# atx_distributor_v1_0.net
KiCad netlist of a schematic drawn in EAGLE
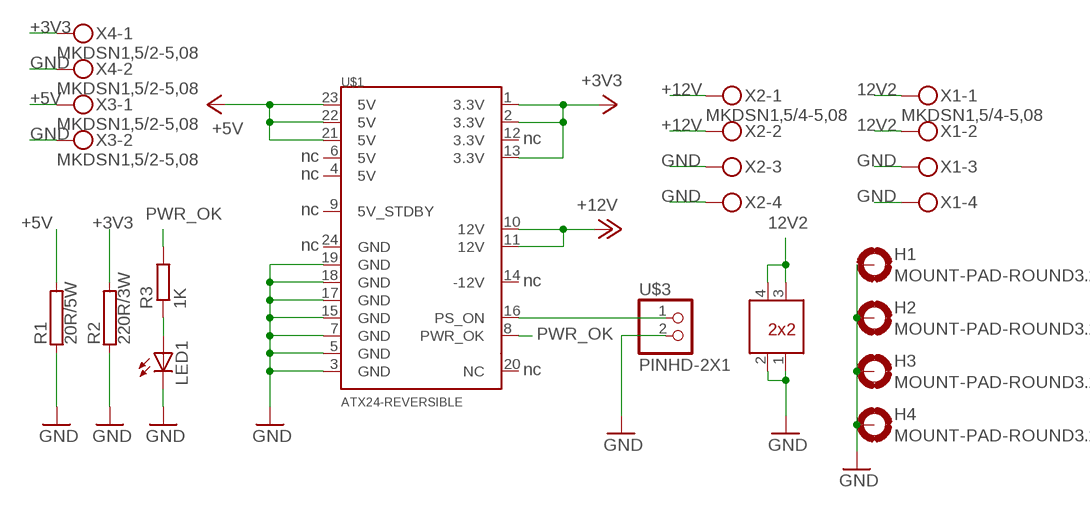
[diagram p0: schematic, sheet 1]

(export (version "E")
  (design (tool "Eeschema 10.0.6"))
  (components
    (comp (ref "H1")
      (value "MOUNT-PAD-ROUND3.2")
      (footprint "eagle-import:3,2-PAD")
      (libsource (lib "eagle-import") (part "MOUNT-PAD-ROUND3.2"))
    )
    (comp (ref "H2")
      (value "MOUNT-PAD-ROUND3.2")
      (footprint "eagle-import:3,2-PAD")
      (libsource (lib "eagle-import") (part "MOUNT-PAD-ROUND3.2"))
    )
    (comp (ref "H3")
      (value "MOUNT-PAD-ROUND3.2")
      (footprint "eagle-import:3,2-PAD")
      (libsource (lib "eagle-import") (part "MOUNT-PAD-ROUND3.2"))
    )
    (comp (ref "H4")
      (value "MOUNT-PAD-ROUND3.2")
      (footprint "eagle-import:3,2-PAD")
      (libsource (lib "eagle-import") (part "MOUNT-PAD-ROUND3.2"))
    )
    (comp (ref "LED1")
      (value "LED3MM")
      (footprint "eagle-import:LED3MM")
      (libsource (lib "eagle-import") (part "LED3MM"))
    )
    (comp (ref "R1")
      (value "20R/5W")
      (footprint "eagle-import:HPS923")
      (libsource (lib "eagle-import") (part "RHPS923"))
    )
    (comp (ref "R2")
      (value "220R/3W")
      (footprint "eagle-import:CA4050")
      (libsource (lib "eagle-import") (part "RCA4050"))
    )
    (comp (ref "R3")
      (value "1K")
      (footprint "eagle-import:0207_10")
      (libsource (lib "eagle-import") (part "R-EU_0207/10"))
    )
    (comp (ref "U$1")
      (value "ATX24-REVERSIBLE")
      (footprint "eagle-import:ATX24")
      (libsource (lib "eagle-import") (part "ATX24-REVERSIBLE"))
    )
    (comp (ref "U$2")
      (value "ATX2X2")
      (footprint "eagle-import:ATX2X2")
      (libsource (lib "eagle-import") (part "ATX2X2"))
    )
    (comp (ref "U$3")
      (value "PINHD-2X1")
      (footprint "eagle-import:PINHD-2X1")
      (libsource (lib "eagle-import") (part "PINHD-2X1"))
    )
    (comp (ref "X1")
      (value "MKDSN1,5/4-5,08")
      (footprint "eagle-import:MKDSN1,5_4-5,08")
      (fields (field (name "MPN") "SMKDSN1,5/4-5,08"))
      (libsource (lib "eagle-import") (part "MKDSN1,5/4-5,08"))
    )
    (comp (ref "X2")
      (value "MKDSN1,5/4-5,08")
      (footprint "eagle-import:MKDSN1,5_4-5,08")
      (fields (field (name "MPN") "SMKDSN1,5/4-5,08"))
      (libsource (lib "eagle-import") (part "MKDSN1,5/4-5,08"))
    )
    (comp (ref "X3")
      (value "MKDSN1,5/2-5,08")
      (footprint "eagle-import:MKDSN1,5_2-5,08")
      (fields (field (name "MPN") "MKDSN 1,5/2-5.08"))
      (libsource (lib "eagle-import") (part "MKDSN1,5/2-5,08"))
    )
    (comp (ref "X4")
      (value "MKDSN1,5/2-5,08")
      (footprint "eagle-import:MKDSN1,5_2-5,08")
      (fields (field (name "MPN") "MKDSN 1,5/2-5.08"))
      (libsource (lib "eagle-import") (part "MKDSN1,5/2-5,08"))
    )
  )
  (nets
    (net (code "1") (name "+3V3") (class "Default")
      (node (ref "R2") (pin "2") (pinfunction "2_2") (pintype "passive"))
      (node (ref "U$1") (pin "1") (pinfunction "3.3V_1") (pintype "bidirectional"))
      (node (ref "U$1") (pin "13") (pinfunction "3.3V_13") (pintype "bidirectional"))
      (node (ref "U$1") (pin "2") (pinfunction "3.3V_2") (pintype "bidirectional"))
      (node (ref "X4") (pin "1") (pinfunction "KL_1") (pintype "passive"))
    )
    (net (code "2") (name "+5V") (class "Default")
      (node (ref "R1") (pin "2") (pinfunction "2_2") (pintype "passive"))
      (node (ref "U$1") (pin "21") (pinfunction "5V_21") (pintype "bidirectional"))
      (node (ref "U$1") (pin "22") (pinfunction "5V_22") (pintype "bidirectional"))
      (node (ref "U$1") (pin "23") (pinfunction "5V_23") (pintype "bidirectional"))
      (node (ref "X3") (pin "1") (pinfunction "KL_1") (pintype "passive"))
    )
    (net (code "3") (name "+12V") (class "Default")
      (node (ref "U$1") (pin "10") (pinfunction "12V_10") (pintype "bidirectional"))
      (node (ref "U$1") (pin "11") (pinfunction "12V_11") (pintype "bidirectional"))
      (node (ref "X2") (pin "1") (pinfunction "KL_1") (pintype "passive"))
      (node (ref "X2") (pin "2") (pinfunction "KL_2") (pintype "passive"))
    )
    (net (code "4") (name "/12V2") (class "Default")
      (node (ref "U$2") (pin "3") (pinfunction "P$3_3") (pintype "bidirectional"))
      (node (ref "U$2") (pin "4") (pinfunction "P$4_4") (pintype "bidirectional"))
      (node (ref "X1") (pin "1") (pinfunction "KL_1") (pintype "passive"))
      (node (ref "X1") (pin "2") (pinfunction "KL_2") (pintype "passive"))
    )
    (net (code "5") (name "/PWR_OK") (class "Default")
      (node (ref "R3") (pin "2") (pinfunction "2_2") (pintype "passive"))
      (node (ref "U$1") (pin "8") (pinfunction "PWR_OK_8") (pintype "bidirectional"))
    )
    (net (code "6") (name "GND") (class "Default")
      (node (ref "H1") (pin "B3,2") (pinfunction "MOUNT_B3,2") (pintype "passive"))
      (node (ref "H2") (pin "B3,2") (pinfunction "MOUNT_B3,2") (pintype "passive"))
      (node (ref "H3") (pin "B3,2") (pinfunction "MOUNT_B3,2") (pintype "passive"))
      (node (ref "H4") (pin "B3,2") (pinfunction "MOUNT_B3,2") (pintype "passive"))
      (node (ref "LED1") (pin "K") (pinfunction "C_K") (pintype "passive"))
      (node (ref "R1") (pin "1") (pinfunction "1_1") (pintype "passive"))
      (node (ref "R2") (pin "1") (pinfunction "1_1") (pintype "passive"))
      (node (ref "U$1") (pin "15") (pinfunction "GND_15") (pintype "bidirectional"))
      (node (ref "U$1") (pin "17") (pinfunction "GND_17") (pintype "bidirectional"))
      (node (ref "U$1") (pin "18") (pinfunction "GND_18") (pintype "bidirectional"))
      (node (ref "U$1") (pin "19") (pinfunction "GND_19") (pintype "bidirectional"))
      (node (ref "U$1") (pin "3") (pinfunction "GND_3") (pintype "bidirectional"))
      (node (ref "U$1") (pin "5") (pinfunction "GND_5") (pintype "bidirectional"))
      (node (ref "U$1") (pin "7") (pinfunction "GND_7") (pintype "bidirectional"))
      (node (ref "U$2") (pin "1") (pinfunction "P$1_1") (pintype "bidirectional"))
      (node (ref "U$2") (pin "2") (pinfunction "P$2_2") (pintype "bidirectional"))
      (node (ref "U$3") (pin "2") (pinfunction "2_2") (pintype "passive"))
      (node (ref "X1") (pin "3") (pinfunction "KL_3") (pintype "passive"))
      (node (ref "X1") (pin "4") (pinfunction "KL_4") (pintype "passive"))
      (node (ref "X2") (pin "3") (pinfunction "KL_3") (pintype "passive"))
      (node (ref "X2") (pin "4") (pinfunction "KL_4") (pintype "passive"))
      (node (ref "X3") (pin "2") (pinfunction "KL_2") (pintype "passive"))
      (node (ref "X4") (pin "2") (pinfunction "KL_2") (pintype "passive"))
    )
    (net (code "7") (name "Net-(LED1-PadA)") (class "Default")
      (node (ref "LED1") (pin "A") (pinfunction "A_A") (pintype "passive"))
      (node (ref "R3") (pin "1") (pinfunction "1_1") (pintype "passive"))
    )
    (net (code "8") (name "Net-(U$1-PS_ON)") (class "Default")
      (node (ref "U$1") (pin "16") (pinfunction "PS_ON_16") (pintype "bidirectional"))
      (node (ref "U$3") (pin "1") (pinfunction "1_1") (pintype "passive"))
    )
    (net (code "9") (name "unconnected-(U$1--12V-Pad14)") (class "Default")
      (node (ref "U$1") (pin "14") (pinfunction "-12V_14") (pintype "bidirectional"))
    )
    (net (code "10") (name "unconnected-(U$1-3.3V-Pad12)") (class "Default")
      (node (ref "U$1") (pin "12") (pinfunction "3.3V_12") (pintype "bidirectional"))
    )
    (net (code "11") (name "unconnected-(U$1-5V-Pad4)") (class "Default")
      (node (ref "U$1") (pin "4") (pinfunction "5V_4") (pintype "bidirectional"))
    )
    (net (code "12") (name "unconnected-(U$1-5V-Pad6)") (class "Default")
      (node (ref "U$1") (pin "6") (pinfunction "5V_6") (pintype "bidirectional"))
    )
    (net (code "13") (name "unconnected-(U$1-5V_STDBY-Pad9)") (class "Default")
      (node (ref "U$1") (pin "9") (pinfunction "5V_STDBY_9") (pintype "bidirectional"))
    )
    (net (code "14") (name "unconnected-(U$1-GND-Pad24)") (class "Default")
      (node (ref "U$1") (pin "24") (pinfunction "GND_24") (pintype "bidirectional"))
    )
    (net (code "15") (name "unconnected-(U$1-NC-Pad20)") (class "Default")
      (node (ref "U$1") (pin "20") (pinfunction "NC_20") (pintype "bidirectional"))
    )
  )
)
